# psu.net
KiCad netlist of a schematic drawn in EAGLE
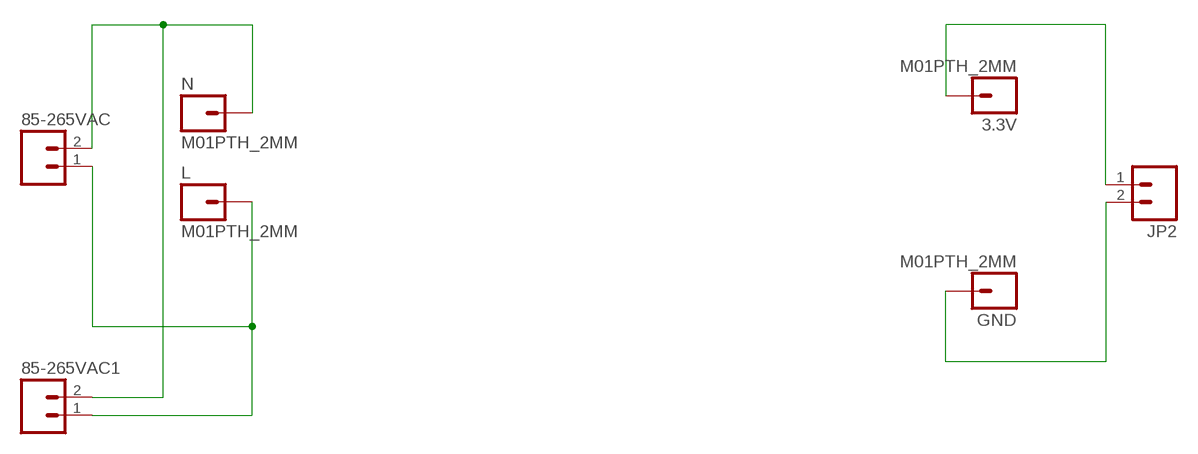
[diagram p0: schematic, sheet 1]

(export (version "E")
  (design (tool "Eeschema 10.0.6"))
  (components
    (comp (ref "3.3V")
      (value "M01PTH_2MM")
      (footprint "eagle-import:1X01_2MM")
      (libsource (lib "eagle-import") (part "M01PTH_2MM"))
    )
    (comp (ref "85-265VAC")
      (value "M02PTH3_5MM")
      (footprint "eagle-import:1X02_LONGPADS")
      (libsource (lib "eagle-import") (part "M02PTH3_5MM"))
    )
    (comp (ref "85-265VAC1")
      (value "M02PTH3_5MM")
      (footprint "eagle-import:1X02_LONGPADS")
      (libsource (lib "eagle-import") (part "M02PTH3_5MM"))
    )
    (comp (ref "GND")
      (value "M01PTH_2MM")
      (footprint "eagle-import:1X01_2MM")
      (libsource (lib "eagle-import") (part "M01PTH_2MM"))
    )
    (comp (ref "JP2")
      (value "M02PTH3_5MM")
      (footprint "eagle-import:1X02_LONGPADS")
      (libsource (lib "eagle-import") (part "M02PTH3_5MM"))
    )
    (comp (ref "L")
      (value "M01PTH_2MM")
      (footprint "eagle-import:1X01_2MM")
      (libsource (lib "eagle-import") (part "M01PTH_2MM"))
    )
    (comp (ref "N")
      (value "M01PTH_2MM")
      (footprint "eagle-import:1X01_2MM")
      (libsource (lib "eagle-import") (part "M01PTH_2MM"))
    )
  )
  (nets
    (net (code "1") (name "Net-(3.3V-Pad1)") (class "Default")
      (node (ref "3.3V") (pin "1") (pinfunction "1_1") (pintype "passive"))
      (node (ref "JP2") (pin "1") (pinfunction "1_1") (pintype "passive"))
    )
    (net (code "2") (name "Net-(85-265VAC-Pad1)") (class "Default")
      (node (ref "85-265VAC") (pin "1") (pinfunction "1_1") (pintype "passive"))
      (node (ref "85-265VAC1") (pin "1") (pinfunction "1_1") (pintype "passive"))
      (node (ref "L") (pin "1") (pinfunction "1_1") (pintype "passive"))
    )
    (net (code "3") (name "Net-(85-265VAC-Pad2)") (class "Default")
      (node (ref "85-265VAC") (pin "2") (pinfunction "2_2") (pintype "passive"))
      (node (ref "85-265VAC1") (pin "2") (pinfunction "2_2") (pintype "passive"))
      (node (ref "N") (pin "1") (pinfunction "1_1") (pintype "passive"))
    )
    (net (code "4") (name "Net-(GND-Pad1)") (class "Default")
      (node (ref "GND") (pin "1") (pinfunction "1_1") (pintype "passive"))
      (node (ref "JP2") (pin "2") (pinfunction "2_2") (pintype "passive"))
    )
  )
)
